# Pulse_WS_MAX30105.net
KiCad netlist of a schematic drawn in Altium Designer
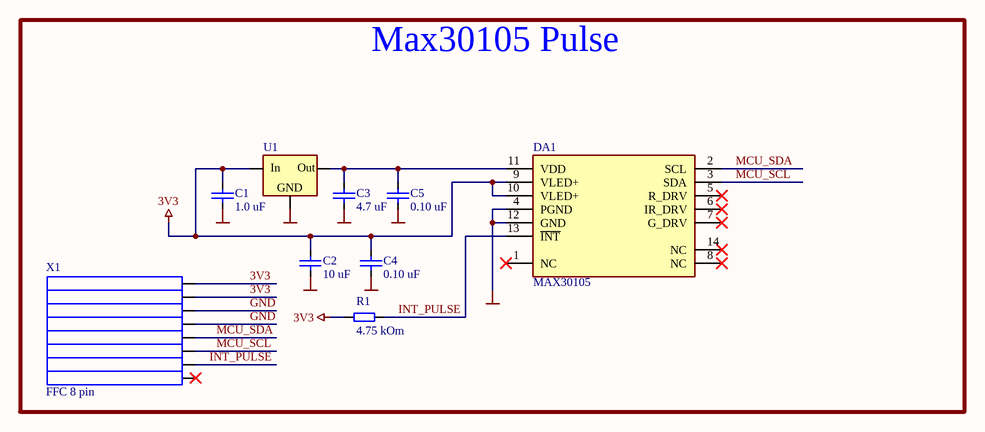
[diagram p0: Pulse_WS_MAX30105.SchDoc]

(export (version "E")
  (design (tool "Eeschema 10.0.6"))
  (components
    (comp (ref "C1")
      (value "1.0 uF")
      (footprint "CAPC1608X90N")
      (fields
        (field (name "MANUFACTURERPARTNUMBER") "GRM188R71C105KA12D")
        (field (name "MANUFACTURER") "muRata")
        (field (name "Comment") "STD_CAP")
      )
      (libsource (lib "Altium_lib") (part "STD_CAP"))
    )
    (comp (ref "C2")
      (value "10 uF")
      (footprint "CAPC2012X120N")
      (fields
        (field (name "MANUFACTURERPARTNUMBER") "GRM21BR71A106KE51L")
        (field (name "MANUFACTURER") "muRata")
        (field (name "Comment") "STD_CAP")
      )
      (libsource (lib "Altium_lib") (part "STD_CAP"))
    )
    (comp (ref "C3")
      (value "4.7 uF")
      (footprint "CAPC2012X120N")
      (fields
        (field (name "MANUFACTURERPARTNUMBER") "GRM21BR71A475KA73L")
        (field (name "MANUFACTURER") "muRata")
        (field (name "Comment") "STD_CAP")
      )
      (libsource (lib "Altium_lib") (part "STD_CAP"))
    )
    (comp (ref "C4")
      (value "0.10 uF")
      (footprint "CAPC1005X55N")
      (fields
        (field (name "MANUFACTURERPARTNUMBER") "GRM155R71C104KA88D")
        (field (name "MANUFACTURER") "muRata")
        (field (name "Comment") "STD_CAP")
        (field (name "AUTHORMODIFICATION_COMP") "anosova")
      )
      (libsource (lib "Altium_lib") (part "STD_CAP"))
    )
    (comp (ref "C5")
      (value "0.10 uF")
      (footprint "CAPC1005X55N")
      (fields
        (field (name "MANUFACTURERPARTNUMBER") "GRM155R71C104KA88D")
        (field (name "MANUFACTURER") "muRata")
        (field (name "Comment") "STD_CAP")
        (field (name "AUTHORMODIFICATION_COMP") "anosova")
      )
      (libsource (lib "Altium_lib") (part "STD_CAP"))
    )
    (comp (ref "DA1")
      (value "MAX30105")
      (footprint "MAX30105")
      (fields
        (field (name "MANUFACTURERPARTNUMBER") "MPU-9250")
        (field (name "MANUFACTURER") "MAX")
        (field (name "COMPONENTLINK1URL") "D:\\HSE\\Трекер физ состояния\\Help\\MAX30105.pdf")
        (field (name "HELPURL") "D:\\HSE\\Трекер физ состояния\\Help\\MAX30105.pdf")
      )
      (libsource (lib "SCH_Wearing_sensor") (part "MAX30105"))
    )
    (comp (ref "R1")
      (value "4.75 kOm")
      (footprint "RESC1005X40N")
      (fields
        (field (name "MANUFACTURERPARTNUMBER") "RC0402FR-074K75L")
        (field (name "MANUFACTURER") "Yageo")
        (field (name "Comment") "STD_RES")
      )
      (libsource (lib "Altium_lib") (part "STD_RES"))
    )
    (comp (ref "U1")
      (value "XC6206P182MR")
      (footprint "SOT23")
      (description "LDO 1v8")
      (fields (field (name "MANUFACTURER") "UMW"))
      (libsource (lib "SCH_Wearing_sensor") (part "XC6206P182MR"))
    )
    (comp (ref "X1")
      (value "FFC 8 pin")
      (footprint "68710814022")
      (description "FFC connector 8 pin")
      (libsource (lib "SCH_Wearing_sensor") (part "FFC 8 pin"))
    )
  )
  (nets
    (net (code "1") (name "/INT_PULSE") (class "Default")
      (node (ref "DA1") (pin "13") (pinfunction "~{INT}_13") (pintype "passive"))
      (node (ref "R1") (pin "2") (pinfunction "2_2") (pintype "passive"))
      (node (ref "X1") (pin "7") (pintype "passive"))
    )
    (net (code "2") (name "/MCU_SCL") (class "Default")
      (node (ref "DA1") (pin "3") (pinfunction "SDA_3") (pintype "passive"))
      (node (ref "X1") (pin "6") (pintype "passive"))
    )
    (net (code "3") (name "/MCU_SDA") (class "Default")
      (node (ref "DA1") (pin "2") (pinfunction "SCL_2") (pintype "passive"))
      (node (ref "X1") (pin "5") (pintype "passive"))
    )
    (net (code "4") (name "3V3") (class "Default")
      (node (ref "C1") (pin "1") (pinfunction "1_1") (pintype "passive"))
      (node (ref "C2") (pin "1") (pinfunction "1_1") (pintype "passive"))
      (node (ref "C4") (pin "1") (pinfunction "1_1") (pintype "passive"))
      (node (ref "DA1") (pin "10") (pinfunction "VLED+_10") (pintype "passive"))
      (node (ref "DA1") (pin "9") (pinfunction "VLED+_9") (pintype "passive"))
      (node (ref "R1") (pin "1") (pinfunction "1_1") (pintype "passive"))
      (node (ref "U1") (pin "3") (pintype "passive"))
      (node (ref "X1") (pin "1") (pintype "passive"))
      (node (ref "X1") (pin "2") (pintype "passive"))
    )
    (net (code "5") (name "GND") (class "Default")
      (node (ref "C1") (pin "2") (pinfunction "2_2") (pintype "passive"))
      (node (ref "C2") (pin "2") (pinfunction "2_2") (pintype "passive"))
      (node (ref "C3") (pin "2") (pinfunction "2_2") (pintype "passive"))
      (node (ref "C4") (pin "2") (pinfunction "2_2") (pintype "passive"))
      (node (ref "C5") (pin "2") (pinfunction "2_2") (pintype "passive"))
      (node (ref "DA1") (pin "12") (pinfunction "GND_12") (pintype "passive"))
      (node (ref "DA1") (pin "4") (pinfunction "PGND_4") (pintype "passive"))
      (node (ref "U1") (pin "1") (pintype "passive"))
      (node (ref "X1") (pin "3") (pintype "passive"))
      (node (ref "X1") (pin "4") (pintype "passive"))
    )
    (net (code "6") (name "Net-(DA1-VDD)") (class "Default")
      (node (ref "C3") (pin "1") (pinfunction "1_1") (pintype "passive"))
      (node (ref "C5") (pin "1") (pinfunction "1_1") (pintype "passive"))
      (node (ref "DA1") (pin "11") (pinfunction "VDD_11") (pintype "passive"))
      (node (ref "U1") (pin "2") (pintype "passive"))
    )
    (net (code "7") (name "unconnected-(DA1-G_DRV-Pad7)") (class "Default")
      (node (ref "DA1") (pin "7") (pinfunction "G_DRV_7") (pintype "passive+no_connect"))
    )
    (net (code "8") (name "unconnected-(DA1-IR_DRV-Pad6)") (class "Default")
      (node (ref "DA1") (pin "6") (pinfunction "IR_DRV_6") (pintype "passive+no_connect"))
    )
    (net (code "9") (name "unconnected-(DA1-NC-Pad1)") (class "Default")
      (node (ref "DA1") (pin "1") (pinfunction "NC_1") (pintype "passive+no_connect"))
    )
    (net (code "10") (name "unconnected-(DA1-NC-Pad8)") (class "Default")
      (node (ref "DA1") (pin "8") (pinfunction "NC_8") (pintype "passive+no_connect"))
    )
    (net (code "11") (name "unconnected-(DA1-NC-Pad14)") (class "Default")
      (node (ref "DA1") (pin "14") (pinfunction "NC_14") (pintype "passive+no_connect"))
    )
    (net (code "12") (name "unconnected-(DA1-R_DRV-Pad5)") (class "Default")
      (node (ref "DA1") (pin "5") (pinfunction "R_DRV_5") (pintype "passive+no_connect"))
    )
    (net (code "13") (name "unconnected-(X1-Pad8)") (class "Default")
      (node (ref "X1") (pin "8") (pintype "passive+no_connect"))
    )
  )
)
